# currentSensor.net
KiCad netlist of a schematic drawn in Altium Designer
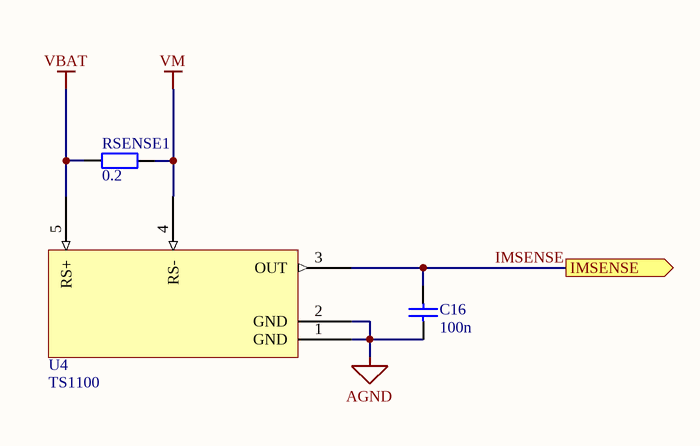
[diagram p0: currentSensor.SchDoc]

(export (version "E")
  (design (tool "Eeschema 10.0.6"))
  (components
    (comp (ref "C16")
      (value "100n")
      (footprint "CAP 0603/1608")
      (libsource (lib "Miscellaneous Devices") (part "Cap"))
    )
    (comp (ref "RSENSE1")
      (value "0.2")
      (footprint "RES 0603/1608")
      (libsource (lib "Miscellaneous Devices") (part "Res2"))
    )
    (comp (ref "U4") (value "TS1100") (footprint "SOT23-5") (libsource (lib "CompoLib") (part "TS1100")))
  )
  (nets
    (net (code "1") (name "/IMSENSE") (class "Default")
      (node (ref "C16") (pin "1") (pinfunction "1_1") (pintype "passive"))
      (node (ref "U4") (pin "3") (pinfunction "OUT_3") (pintype "output"))
    )
    (net (code "2") (name "AGND") (class "Default")
      (node (ref "C16") (pin "2") (pinfunction "2_2") (pintype "passive"))
      (node (ref "U4") (pin "1") (pinfunction "GND_1") (pintype "power_in"))
      (node (ref "U4") (pin "2") (pinfunction "GND_2") (pintype "power_in"))
    )
    (net (code "3") (name "VBAT") (class "Default")
      (node (ref "RSENSE1") (pin "1") (pinfunction "1_1") (pintype "passive"))
      (node (ref "U4") (pin "5") (pinfunction "RS+_5") (pintype "input"))
    )
    (net (code "4") (name "VM") (class "Default")
      (node (ref "RSENSE1") (pin "2") (pinfunction "2_2") (pintype "passive"))
      (node (ref "U4") (pin "4") (pinfunction "RS-_4") (pintype "input"))
    )
  )
)
